# BMS_Schematic.net
KiCad netlist of a schematic drawn in EAGLE
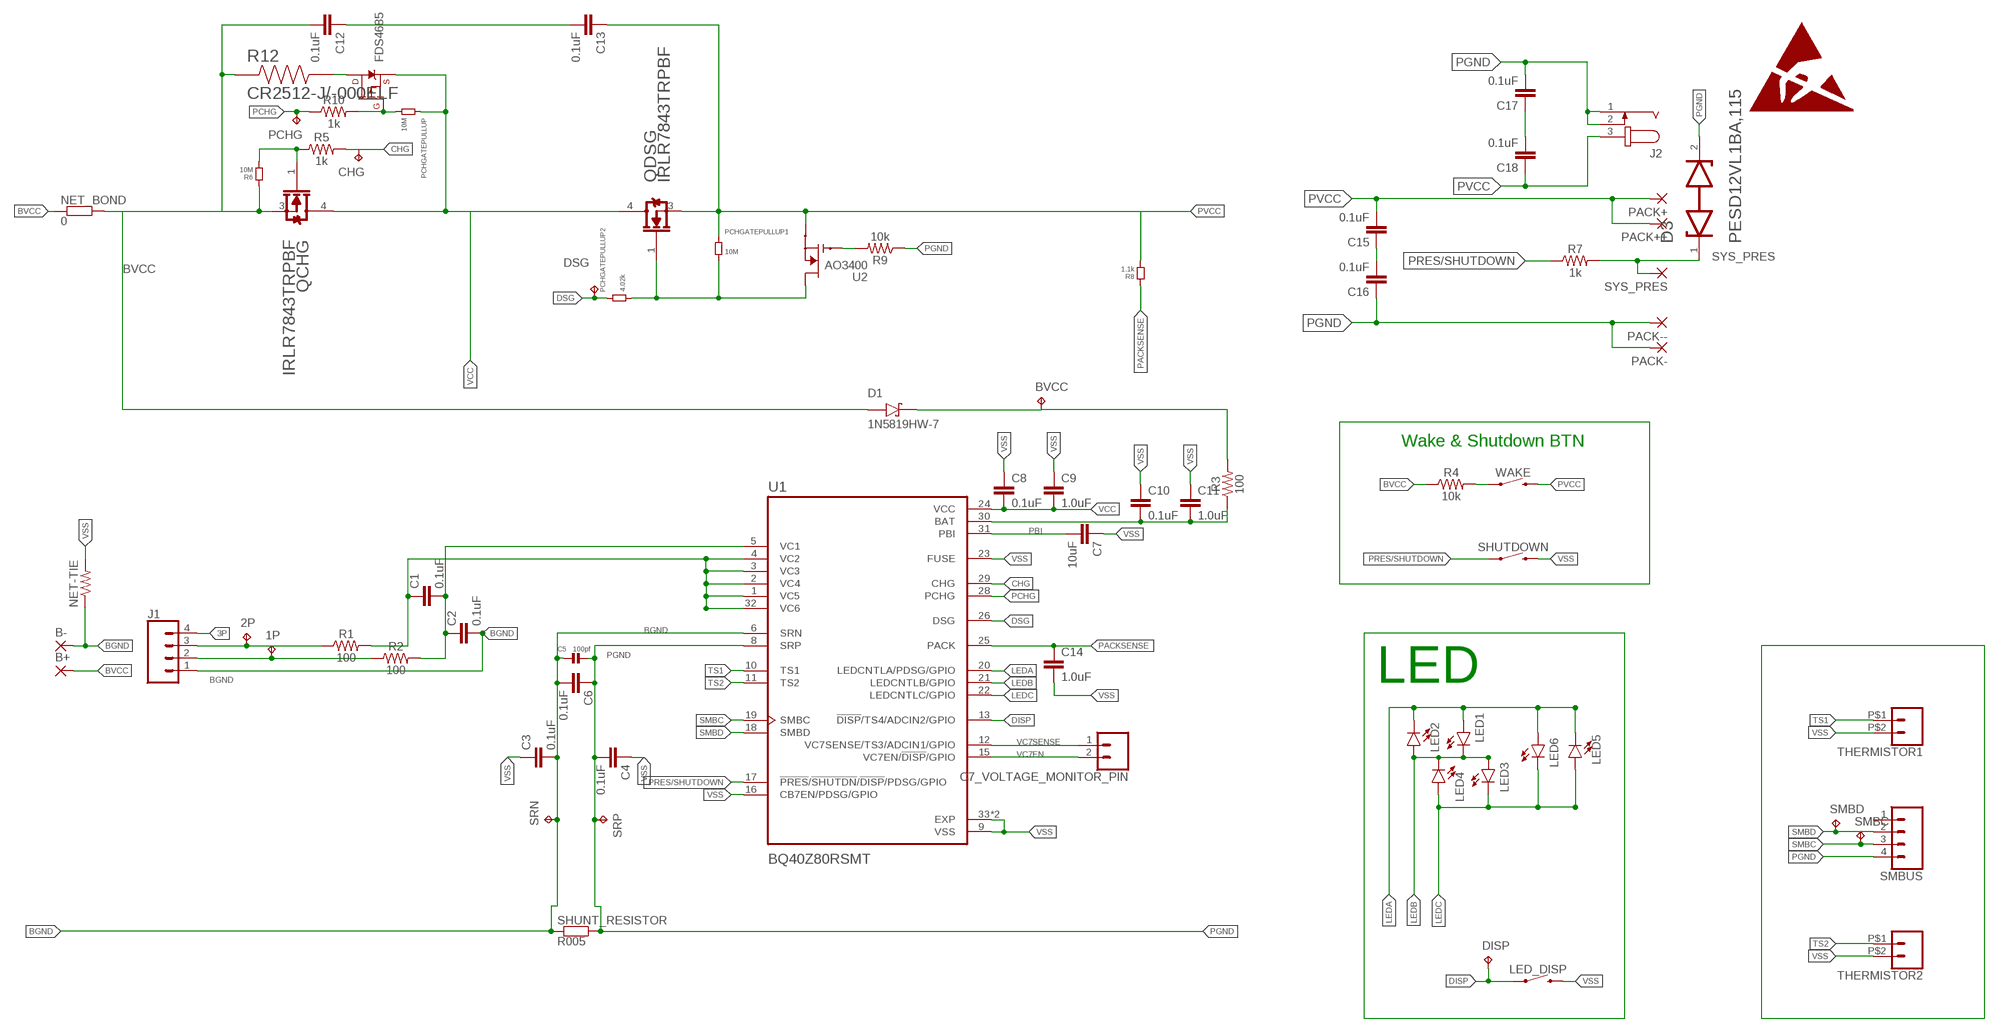
[diagram p0: schematic, sheet 1]

(export (version "E")
  (design (tool "Eeschema 10.0.6"))
  (components
    (comp (ref "1P")
      (value "TPTP10R")
      (footprint "eagle-import:TP10R")
      (libsource (lib "eagle-import") (part "TPTP10R"))
    )
    (comp (ref "2P")
      (value "TPTP10R")
      (footprint "eagle-import:TP10R")
      (libsource (lib "eagle-import") (part "TPTP10R"))
    )
    (comp (ref "B+")
      (value "WIREPADSMD5-2,5")
      (footprint "eagle-import:5-2,5")
      (libsource (lib "eagle-import") (part "WIREPADSMD5-2,5"))
    )
    (comp (ref "B-")
      (value "WIREPADSMD5-2,5")
      (footprint "eagle-import:5-2,5")
      (libsource (lib "eagle-import") (part "WIREPADSMD5-2,5"))
    )
    (comp (ref "BVCC")
      (value "TPTP10R")
      (footprint "eagle-import:TP10R")
      (libsource (lib "eagle-import") (part "TPTP10R"))
    )
    (comp (ref "C1")
      (value "0.1uF")
      (footprint "eagle-import:0603")
      (libsource (lib "eagle-import") (part "0.1UF-0603-25V-5%"))
    )
    (comp (ref "C2")
      (value "0.1uF")
      (footprint "eagle-import:0603")
      (libsource (lib "eagle-import") (part "0.1UF-0603-25V-5%"))
    )
    (comp (ref "C3")
      (value "0.1uF")
      (footprint "eagle-import:0603")
      (libsource (lib "eagle-import") (part "0.1UF-0603-25V-5%"))
    )
    (comp (ref "C4")
      (value "0.1uF")
      (footprint "eagle-import:0603")
      (libsource (lib "eagle-import") (part "0.1UF-0603-25V-5%"))
    )
    (comp (ref "C5")
      (value "100pf")
      (footprint "eagle-import:0805")
      (libsource (lib "eagle-import") (part "CAPACITOR.0805"))
    )
    (comp (ref "C6")
      (value "0.1uF")
      (footprint "eagle-import:0603")
      (libsource (lib "eagle-import") (part "0.1UF-0603-25V-5%"))
    )
    (comp (ref "C7")
      (value "10uF")
      (footprint "eagle-import:0603")
      (libsource (lib "eagle-import") (part "10UF-0603-6.3V-20%"))
    )
    (comp (ref "C7_VOLTAGE_MONITOR_PIN")
      (value "CONN_02")
      (footprint "eagle-import:1X02")
      (libsource (lib "eagle-import") (part "CONN_02"))
    )
    (comp (ref "C8")
      (value "0.1uF")
      (footprint "eagle-import:0603")
      (libsource (lib "eagle-import") (part "0.1UF-0603-25V-(+80/-20%)"))
    )
    (comp (ref "C9")
      (value "1.0uF")
      (footprint "eagle-import:0603")
      (libsource (lib "eagle-import") (part "1.0UF-0603-16V-10%-X7R"))
    )
    (comp (ref "C10")
      (value "0.1uF")
      (footprint "eagle-import:0603")
      (libsource (lib "eagle-import") (part "0.1UF-0603-25V-(+80/-20%)"))
    )
    (comp (ref "C11")
      (value "1.0uF")
      (footprint "eagle-import:0603")
      (libsource (lib "eagle-import") (part "1.0UF-0603-16V-10%-X7R"))
    )
    (comp (ref "C12")
      (value "0.1uF")
      (footprint "eagle-import:0603")
      (libsource (lib "eagle-import") (part "0.1UF-0603-25V-(+80/-20%)"))
    )
    (comp (ref "C13")
      (value "0.1uF")
      (footprint "eagle-import:0603")
      (libsource (lib "eagle-import") (part "0.1UF-0603-25V-(+80/-20%)"))
    )
    (comp (ref "C14")
      (value "1.0uF")
      (footprint "eagle-import:0603")
      (libsource (lib "eagle-import") (part "1.0UF-0603-16V-10%-X7R"))
    )
    (comp (ref "C15")
      (value "0.1uF")
      (footprint "eagle-import:0603")
      (libsource (lib "eagle-import") (part "0.1UF-0603-25V-(+80/-20%)"))
    )
    (comp (ref "C16")
      (value "0.1uF")
      (footprint "eagle-import:0603")
      (libsource (lib "eagle-import") (part "0.1UF-0603-25V-(+80/-20%)"))
    )
    (comp (ref "C17")
      (value "0.1uF")
      (footprint "eagle-import:0603")
      (libsource (lib "eagle-import") (part "0.1UF-0603-25V-(+80/-20%)"))
    )
    (comp (ref "C18")
      (value "0.1uF")
      (footprint "eagle-import:0603")
      (libsource (lib "eagle-import") (part "0.1UF-0603-25V-(+80/-20%)"))
    )
    (comp (ref "CHG")
      (value "TPTP10R")
      (footprint "eagle-import:TP10R")
      (libsource (lib "eagle-import") (part "TPTP10R"))
    )
    (comp (ref "D1")
      (value "1N5819HW-7")
      (footprint "eagle-import:SOD3715X145N")
      (fields (field (name "MF") "Diodes Inc."))
      (libsource (lib "eagle-import") (part "1N5819HW-7"))
    )
    (comp (ref "D3")
      (value "NEXPERIA_PESD12VL1BA,115NEXPERIA_PESD12VL1BA,115_0_0")
      (footprint "eagle-import:NEXPERIA_PESD12VL1BA,115_0")
      (fields
        (field (name "DIGIKEY_PART_NUMBER") "1727-3808-1-ND")
        (field (name "MF") "Nexperia")
        (field (name "MOUSER_PART_NUMBER") "771-PESD12VL1BA-T/R")
      )
      (libsource (lib "eagle-import") (part "NEXPERIA_PESD12VL1BA,115NEXPERIA_PESD12VL1BA,115_0_0"))
    )
    (comp (ref "DISP")
      (value "TPTP10R")
      (footprint "eagle-import:TP10R")
      (libsource (lib "eagle-import") (part "TPTP10R"))
    )
    (comp (ref "DSG")
      (value "TPTP10R")
      (footprint "eagle-import:TP10R")
      (libsource (lib "eagle-import") (part "TPTP10R"))
    )
    (comp (ref "J1")
      (value "CONN_04JST-PTH")
      (footprint "eagle-import:JST-4-PTH")
      (libsource (lib "eagle-import") (part "CONN_04JST-PTH"))
    )
    (comp (ref "J2")
      (value "JACK-PLUG0")
      (footprint "eagle-import:SPC4077")
      (libsource (lib "eagle-import") (part "JACK-PLUG0"))
    )
    (comp (ref "LED1")
      (value "GREEN")
      (footprint "eagle-import:LED-0603")
      (libsource (lib "eagle-import") (part "LED-GREEN0603"))
    )
    (comp (ref "LED2")
      (value "GREEN")
      (footprint "eagle-import:LED-0603")
      (libsource (lib "eagle-import") (part "LED-GREEN0603"))
    )
    (comp (ref "LED3")
      (value "GREEN")
      (footprint "eagle-import:LED-0603")
      (libsource (lib "eagle-import") (part "LED-GREEN0603"))
    )
    (comp (ref "LED4")
      (value "GREEN")
      (footprint "eagle-import:LED-0603")
      (libsource (lib "eagle-import") (part "LED-GREEN0603"))
    )
    (comp (ref "LED5")
      (value "GREEN")
      (footprint "eagle-import:LED-0603")
      (libsource (lib "eagle-import") (part "LED-GREEN0603"))
    )
    (comp (ref "LED6")
      (value "GREEN")
      (footprint "eagle-import:LED-0603")
      (libsource (lib "eagle-import") (part "LED-GREEN0603"))
    )
    (comp (ref "LED_DISP")
      (value "MOMENTARY-SWITCH-SPST-SMD-6.0X3.5MM")
      (footprint "eagle-import:TACTILE_SWITCH_SMD_6.0X3.5MM")
      (libsource (lib "eagle-import") (part "MOMENTARY-SWITCH-SPST-SMD-6.0X3.5MM"))
    )
    (comp (ref "NET-TIE")
      (value "0")
      (footprint "eagle-import:0402-TIGHT")
      (libsource (lib "eagle-import") (part "0OHM-0402T-1/10W"))
    )
    (comp (ref "NET_BOND")
      (value "0")
      (footprint "eagle-import:BVS")
      (libsource (lib "eagle-import") (part "BVS"))
    )
    (comp (ref "PACK+")
      (value "WIREPADSMD5-2,5")
      (footprint "eagle-import:5-2,5")
      (libsource (lib "eagle-import") (part "WIREPADSMD5-2,5"))
    )
    (comp (ref "PACK++")
      (value "WIREPADSMD5-2,5")
      (footprint "eagle-import:5-2,5")
      (libsource (lib "eagle-import") (part "WIREPADSMD5-2,5"))
    )
    (comp (ref "PACK-")
      (value "WIREPADSMD5-2,5")
      (footprint "eagle-import:5-2,5")
      (libsource (lib "eagle-import") (part "WIREPADSMD5-2,5"))
    )
    (comp (ref "PACK--")
      (value "WIREPADSMD5-2,5")
      (footprint "eagle-import:5-2,5")
      (libsource (lib "eagle-import") (part "WIREPADSMD5-2,5"))
    )
    (comp (ref "PCHG")
      (value "TPTP10R")
      (footprint "eagle-import:TP10R")
      (libsource (lib "eagle-import") (part "TPTP10R"))
    )
    (comp (ref "PCHGATEPULLUP")
      (value "10M")
      (footprint "eagle-import:0805")
      (libsource (lib "eagle-import") (part "RESISTOR.0805"))
    )
    (comp (ref "PCHGATEPULLUP1")
      (value "10M")
      (footprint "eagle-import:0805")
      (libsource (lib "eagle-import") (part "RESISTOR.0805"))
    )
    (comp (ref "PCHGATEPULLUP2")
      (value "4.02k")
      (footprint "eagle-import:0805")
      (libsource (lib "eagle-import") (part "RESISTOR.0805"))
    )
    (comp (ref "QCHG")
      (value "INFINEON_IRLR7843TRPBFINFINEON_IRLR7843TRPBF_0_0")
      (footprint "eagle-import:INFINEON_IRLR7843TRPBF_0")
      (fields
        (field (name "DIGIKEY_PART_NUMBER") "IRLR7843PBFCT-ND")
        (field (name "MF") "Infineon")
        (field (name "MOUSER_PART_NUMBER") "942-IRLR7843TRPBF")
      )
      (libsource (lib "eagle-import") (part "INFINEON_IRLR7843TRPBFINFINEON_IRLR7843TRPBF_0_0"))
    )
    (comp (ref "QDSG")
      (value "INFINEON_IRLR7843TRPBFINFINEON_IRLR7843TRPBF_0_0")
      (footprint "eagle-import:INFINEON_IRLR7843TRPBF_0")
      (fields
        (field (name "DIGIKEY_PART_NUMBER") "IRLR7843PBFCT-ND")
        (field (name "MF") "Infineon")
        (field (name "MOUSER_PART_NUMBER") "942-IRLR7843TRPBF")
      )
      (libsource (lib "eagle-import") (part "INFINEON_IRLR7843TRPBFINFINEON_IRLR7843TRPBF_0_0"))
    )
    (comp (ref "R1")
      (value "100")
      (footprint "eagle-import:0603")
      (libsource (lib "eagle-import") (part "100OHM-0603-1/10W-1%"))
    )
    (comp (ref "R2")
      (value "100")
      (footprint "eagle-import:0603")
      (libsource (lib "eagle-import") (part "100OHM-0603-1/10W-1%"))
    )
    (comp (ref "R3")
      (value "100")
      (footprint "eagle-import:0603")
      (libsource (lib "eagle-import") (part "100OHM-0603-1/10W-1%"))
    )
    (comp (ref "R4")
      (value "10k")
      (footprint "eagle-import:0603")
      (libsource (lib "eagle-import") (part "10KOHM-0603-1/10W-1%"))
    )
    (comp (ref "R5")
      (value "1k")
      (footprint "eagle-import:0603")
      (libsource (lib "eagle-import") (part "1KOHM-0603-1/10W-1%"))
    )
    (comp (ref "R6")
      (value "10M")
      (footprint "eagle-import:0805")
      (libsource (lib "eagle-import") (part "RESISTOR.0805"))
    )
    (comp (ref "R7")
      (value "1k")
      (footprint "eagle-import:0603")
      (libsource (lib "eagle-import") (part "1KOHM-0603-1/10W-1%"))
    )
    (comp (ref "R8")
      (value "1.1k")
      (footprint "eagle-import:0805")
      (libsource (lib "eagle-import") (part "RESISTOR.0805"))
    )
    (comp (ref "R9")
      (value "10k")
      (footprint "eagle-import:0603")
      (libsource (lib "eagle-import") (part "10KOHM-0603-1/10W-1%"))
    )
    (comp (ref "R10")
      (value "1k")
      (footprint "eagle-import:0603")
      (libsource (lib "eagle-import") (part "1KOHM-0603-1/10W-1%"))
    )
    (comp (ref "R12")
      (value "CR2512-J/-000ELF")
      (footprint "eagle-import:RESC6331X75N")
      (fields (field (name "MF") "Bourns"))
      (libsource (lib "eagle-import") (part "CR2512-J/-000ELF"))
    )
    (comp (ref "SHUNT_RESISTOR")
      (value "R005")
      (footprint "eagle-import:BVS")
      (libsource (lib "eagle-import") (part "BVS"))
    )
    (comp (ref "SHUTDOWN")
      (value "MOMENTARY-SWITCH-SPST-SMD-6.0X3.5MM")
      (footprint "eagle-import:TACTILE_SWITCH_SMD_6.0X3.5MM")
      (libsource (lib "eagle-import") (part "MOMENTARY-SWITCH-SPST-SMD-6.0X3.5MM"))
    )
    (comp (ref "SMBC")
      (value "TPTP10R")
      (footprint "eagle-import:TP10R")
      (libsource (lib "eagle-import") (part "TPTP10R"))
    )
    (comp (ref "SMBD")
      (value "TPTP10R")
      (footprint "eagle-import:TP10R")
      (libsource (lib "eagle-import") (part "TPTP10R"))
    )
    (comp (ref "SMBUS")
      (value "CONN_04JST-SMD-LOCKING")
      (footprint "eagle-import:JST-4-SMD-1.25MM-LOCKING")
      (libsource (lib "eagle-import") (part "CONN_04JST-SMD-LOCKING"))
    )
    (comp (ref "SRN")
      (value "TPTP10R")
      (footprint "eagle-import:TP10R")
      (libsource (lib "eagle-import") (part "TPTP10R"))
    )
    (comp (ref "SRP")
      (value "TPTP10R")
      (footprint "eagle-import:TP10R")
      (libsource (lib "eagle-import") (part "TPTP10R"))
    )
    (comp (ref "SYS_PRES")
      (value "SMD2")
      (footprint "eagle-import:SMD1,27-2,54")
      (libsource (lib "eagle-import") (part "SMD2"))
    )
    (comp (ref "THERMISTOR1")
      (value "SOLDER_PAD_2")
      (footprint "eagle-import:SOLDER_PAD_2")
      (libsource (lib "eagle-import") (part "SOLDER_PAD_2"))
    )
    (comp (ref "THERMISTOR2")
      (value "SOLDER_PAD_2")
      (footprint "eagle-import:SOLDER_PAD_2")
      (libsource (lib "eagle-import") (part "SOLDER_PAD_2"))
    )
    (comp (ref "U$2")
      (value "FDS4685")
      (footprint "eagle-import:SOIC127P600X150-8N")
      (libsource (lib "eagle-import") (part "FDS4685"))
    )
    (comp (ref "U1")
      (value "BQ40Z80RSMT")
      (footprint "eagle-import:QFN40P400X400X100-33N")
      (fields (field (name "MF") "Texas Instruments"))
      (libsource (lib "eagle-import") (part "BQ40Z80RSMT"))
    )
    (comp (ref "U2")
      (value "AO3400")
      (footprint "eagle-import:SOT23")
      (fields (field (name "MF") "Alpha &"))
      (libsource (lib "eagle-import") (part "AO3400"))
    )
    (comp (ref "WAKE")
      (value "MOMENTARY-SWITCH-SPST-SMD-6.0X3.5MM")
      (footprint "eagle-import:TACTILE_SWITCH_SMD_6.0X3.5MM")
      (libsource (lib "eagle-import") (part "MOMENTARY-SWITCH-SPST-SMD-6.0X3.5MM"))
    )
  )
  (nets
    (net (code "1") (name "/PBI") (class "Default")
      (node (ref "C7") (pin "2") (pinfunction "2_2") (pintype "passive"))
      (node (ref "U1") (pin "31") (pinfunction "PBI_31") (pintype "power_in"))
    )
    (net (code "2") (name "/SYS_PRES") (class "Default")
      (node (ref "D3") (pin "1") (pinfunction "CATHODE_1_1") (pintype "passive"))
      (node (ref "R7") (pin "2") (pinfunction "2_2") (pintype "passive"))
      (node (ref "SYS_PRES") (pin "1") (pinfunction "P_1") (pintype "passive"))
    )
    (net (code "3") (name "/VC7EN") (class "Default")
      (node (ref "C7_VOLTAGE_MONITOR_PIN") (pin "2") (pinfunction "2_2") (pintype "passive"))
      (node (ref "U1") (pin "15") (pinfunction "VC7EN/~{DISP}/GPIO_15") (pintype "bidirectional"))
    )
    (net (code "4") (name "/VC7SENSE") (class "Default")
      (node (ref "C7_VOLTAGE_MONITOR_PIN") (pin "1") (pinfunction "1_1") (pintype "passive"))
      (node (ref "U1") (pin "12") (pinfunction "VC7SENSE/TS3/ADCIN1/GPIO_12") (pintype "bidirectional"))
    )
    (net (code "5") (name "3P") (class "Default")
      (node (ref "J1") (pin "4") (pinfunction "4_4") (pintype "passive"))
    )
    (net (code "6") (name "BGND") (class "Default")
      (node (ref "B-") (pin "1") (pinfunction "P_1") (pintype "passive"))
      (node (ref "C2") (pin "2") (pinfunction "2_2") (pintype "passive"))
      (node (ref "C3") (pin "2") (pinfunction "2_2") (pintype "passive"))
      (node (ref "C5") (pin "1") (pinfunction "1_1") (pintype "bidirectional"))
      (node (ref "C6") (pin "2") (pinfunction "2_2") (pintype "passive"))
      (node (ref "J1") (pin "1") (pinfunction "1_1") (pintype "passive"))
      (node (ref "NET-TIE") (pin "1") (pinfunction "1_1") (pintype "passive"))
      (node (ref "SHUNT_RESISTOR") (pin "2") (pinfunction "2_2") (pintype "passive"))
      (node (ref "SRN") (pin "TP") (pinfunction "TP_TP") (pintype "input"))
      (node (ref "U1") (pin "6") (pinfunction "SRN_6") (pintype "input"))
    )
    (net (code "7") (name "BVCC") (class "Default")
      (node (ref "B+") (pin "1") (pinfunction "P_1") (pintype "passive"))
      (node (ref "C12") (pin "2") (pinfunction "2_2") (pintype "passive"))
      (node (ref "D1") (pin "A") (pinfunction "A_A") (pintype "passive"))
      (node (ref "NET_BOND") (pin "1") (pinfunction "1_1") (pintype "passive"))
      (node (ref "NET_BOND") (pin "2") (pinfunction "2_2") (pintype "passive"))
      (node (ref "QCHG") (pin "3") (pinfunction "SOURCE_3") (pintype "passive"))
      (node (ref "R12") (pin "1") (pinfunction "1_1") (pintype "passive"))
      (node (ref "R4") (pin "1") (pinfunction "1_1") (pintype "passive"))
      (node (ref "R6") (pin "1") (pinfunction "1_1") (pintype "bidirectional"))
    )
    (net (code "8") (name "CHG") (class "Default")
      (node (ref "CHG") (pin "TP") (pinfunction "TP_TP") (pintype "input"))
      (node (ref "R5") (pin "2") (pinfunction "2_2") (pintype "passive"))
      (node (ref "U1") (pin "29") (pinfunction "CHG_29") (pintype "output"))
    )
    (net (code "9") (name "DISP") (class "Default")
      (node (ref "DISP") (pin "TP") (pinfunction "TP_TP") (pintype "input"))
      (node (ref "LED_DISP") (pin "1") (pinfunction "1_1") (pintype "passive"))
      (node (ref "U1") (pin "13") (pinfunction "~{DISP}/TS4/ADCIN2/GPIO_13") (pintype "bidirectional"))
    )
    (net (code "10") (name "DSG") (class "Default")
      (node (ref "DSG") (pin "TP") (pinfunction "TP_TP") (pintype "input"))
      (node (ref "PCHGATEPULLUP2") (pin "1") (pinfunction "1_1") (pintype "bidirectional"))
      (node (ref "U1") (pin "26") (pinfunction "DSG_26") (pintype "output"))
    )
    (net (code "11") (name "LEDA") (class "Default")
      (node (ref "LED1") (pin "A") (pinfunction "A_A") (pintype "passive"))
      (node (ref "LED2") (pin "C") (pinfunction "C_C") (pintype "passive"))
      (node (ref "LED5") (pin "C") (pinfunction "C_C") (pintype "passive"))
      (node (ref "LED6") (pin "A") (pinfunction "A_A") (pintype "passive"))
      (node (ref "U1") (pin "20") (pinfunction "LEDCNTLA/PDSG/GPIO_20") (pintype "output"))
    )
    (net (code "12") (name "LEDB") (class "Default")
      (node (ref "LED1") (pin "C") (pinfunction "C_C") (pintype "passive"))
      (node (ref "LED2") (pin "A") (pinfunction "A_A") (pintype "passive"))
      (node (ref "LED3") (pin "A") (pinfunction "A_A") (pintype "passive"))
      (node (ref "LED4") (pin "C") (pinfunction "C_C") (pintype "passive"))
      (node (ref "U1") (pin "21") (pinfunction "LEDCNTLB/GPIO_21") (pintype "output"))
    )
    (net (code "13") (name "LEDC") (class "Default")
      (node (ref "LED3") (pin "C") (pinfunction "C_C") (pintype "passive"))
      (node (ref "LED4") (pin "A") (pinfunction "A_A") (pintype "passive"))
      (node (ref "LED5") (pin "A") (pinfunction "A_A") (pintype "passive"))
      (node (ref "LED6") (pin "C") (pinfunction "C_C") (pintype "passive"))
      (node (ref "U1") (pin "22") (pinfunction "LEDCNTLC/GPIO_22") (pintype "output"))
    )
    (net (code "14") (name "Net-(1P-PadTP)") (class "Default")
      (node (ref "1P") (pin "TP") (pinfunction "TP_TP") (pintype "input"))
      (node (ref "J1") (pin "2") (pinfunction "2_2") (pintype "passive"))
      (node (ref "R2") (pin "1") (pinfunction "1_1") (pintype "passive"))
    )
    (net (code "15") (name "Net-(2P-PadTP)") (class "Default")
      (node (ref "2P") (pin "TP") (pinfunction "TP_TP") (pintype "input"))
      (node (ref "J1") (pin "3") (pinfunction "3_3") (pintype "passive"))
      (node (ref "R1") (pin "1") (pinfunction "1_1") (pintype "passive"))
    )
    (net (code "16") (name "Net-(C12-Pad1)") (class "Default")
      (node (ref "C12") (pin "1") (pinfunction "1_1") (pintype "passive"))
      (node (ref "C13") (pin "2") (pinfunction "2_2") (pintype "passive"))
    )
    (net (code "17") (name "Net-(C15-Pad1)") (class "Default")
      (node (ref "C15") (pin "1") (pinfunction "1_1") (pintype "passive"))
      (node (ref "C16") (pin "2") (pinfunction "2_2") (pintype "passive"))
    )
    (net (code "18") (name "Net-(C17-Pad1)") (class "Default")
      (node (ref "C17") (pin "1") (pinfunction "1_1") (pintype "passive"))
      (node (ref "C18") (pin "2") (pinfunction "2_2") (pintype "passive"))
    )
    (net (code "19") (name "Net-(D1-K)") (class "Default")
      (node (ref "BVCC") (pin "TP") (pinfunction "TP_TP") (pintype "input"))
      (node (ref "D1") (pin "C") (pinfunction "K_C") (pintype "passive"))
      (node (ref "R3") (pin "2") (pinfunction "2_2") (pintype "passive"))
    )
    (net (code "20") (name "Net-(QCHG-GATE)") (class "Default")
      (node (ref "QCHG") (pin "1") (pinfunction "GATE_1") (pintype "passive"))
      (node (ref "R5") (pin "1") (pinfunction "1_1") (pintype "passive"))
      (node (ref "R6") (pin "2") (pinfunction "2_2") (pintype "bidirectional"))
    )
    (net (code "21") (name "Net-(QDSG-GATE)") (class "Default")
      (node (ref "PCHGATEPULLUP1") (pin "2") (pinfunction "2_2") (pintype "bidirectional"))
      (node (ref "PCHGATEPULLUP2") (pin "2") (pinfunction "2_2") (pintype "bidirectional"))
      (node (ref "QDSG") (pin "1") (pinfunction "GATE_1") (pintype "passive"))
      (node (ref "U2") (pin "3") (pinfunction "D_3") (pintype "passive"))
    )
    (net (code "22") (name "Net-(R4-Pad2)") (class "Default")
      (node (ref "R4") (pin "2") (pinfunction "2_2") (pintype "passive"))
      (node (ref "WAKE") (pin "1") (pinfunction "1_1") (pintype "passive"))
    )
    (net (code "23") (name "Net-(R12-Pad2)") (class "Default")
      (node (ref "R12") (pin "2") (pinfunction "2_2") (pintype "passive"))
      (node (ref "U$2") (pin "5") (pinfunction "D_5") (pintype "bidirectional"))
      (node (ref "U$2") (pin "6") (pinfunction "D_6") (pintype "bidirectional"))
      (node (ref "U$2") (pin "7") (pinfunction "D_7") (pintype "bidirectional"))
      (node (ref "U$2") (pin "8") (pinfunction "D_8") (pintype "bidirectional"))
    )
    (net (code "24") (name "Net-(U$2-G)") (class "Default")
      (node (ref "PCHGATEPULLUP") (pin "2") (pinfunction "2_2") (pintype "bidirectional"))
      (node (ref "R10") (pin "2") (pinfunction "2_2") (pintype "passive"))
      (node (ref "U$2") (pin "4") (pinfunction "G_4") (pintype "bidirectional"))
    )
    (net (code "25") (name "Net-(U1-BAT)") (class "Default")
      (node (ref "C10") (pin "2") (pinfunction "2_2") (pintype "passive"))
      (node (ref "C11") (pin "2") (pinfunction "2_2") (pintype "passive"))
      (node (ref "R3") (pin "1") (pinfunction "1_1") (pintype "passive"))
      (node (ref "U1") (pin "30") (pinfunction "BAT_30") (pintype "power_in"))
    )
    (net (code "26") (name "Net-(U1-VC1)") (class "Default")
      (node (ref "C1") (pin "2") (pinfunction "2_2") (pintype "passive"))
      (node (ref "C2") (pin "1") (pinfunction "1_1") (pintype "passive"))
      (node (ref "R2") (pin "2") (pinfunction "2_2") (pintype "passive"))
      (node (ref "U1") (pin "5") (pinfunction "VC1_5") (pintype "input"))
    )
    (net (code "27") (name "Net-(U1-VC2)") (class "Default")
      (node (ref "C1") (pin "1") (pinfunction "1_1") (pintype "passive"))
      (node (ref "R1") (pin "2") (pinfunction "2_2") (pintype "passive"))
      (node (ref "U1") (pin "1") (pinfunction "VC5_1") (pintype "input"))
      (node (ref "U1") (pin "2") (pinfunction "VC4_2") (pintype "input"))
      (node (ref "U1") (pin "3") (pinfunction "VC3_3") (pintype "input"))
      (node (ref "U1") (pin "32") (pinfunction "VC6_32") (pintype "input"))
      (node (ref "U1") (pin "4") (pinfunction "VC2_4") (pintype "input"))
    )
    (net (code "28") (name "Net-(U2-G)") (class "Default")
      (node (ref "R9") (pin "2") (pinfunction "2_2") (pintype "passive"))
      (node (ref "U2") (pin "1") (pinfunction "G_1") (pintype "passive"))
    )
    (net (code "29") (name "PACKSENSE") (class "Default")
      (node (ref "C14") (pin "1") (pinfunction "1_1") (pintype "passive"))
      (node (ref "R8") (pin "1") (pinfunction "1_1") (pintype "bidirectional"))
      (node (ref "U1") (pin "25") (pinfunction "PACK_25") (pintype "input"))
    )
    (net (code "30") (name "PCHG") (class "Default")
      (node (ref "PCHG") (pin "TP") (pinfunction "TP_TP") (pintype "input"))
      (node (ref "R10") (pin "1") (pinfunction "1_1") (pintype "passive"))
      (node (ref "U1") (pin "28") (pinfunction "PCHG_28") (pintype "output"))
    )
    (net (code "31") (name "PGND") (class "Default")
      (node (ref "C16") (pin "1") (pinfunction "1_1") (pintype "passive"))
      (node (ref "C17") (pin "2") (pinfunction "2_2") (pintype "passive"))
      (node (ref "C4") (pin "2") (pinfunction "2_2") (pintype "passive"))
      (node (ref "C5") (pin "2") (pinfunction "2_2") (pintype "bidirectional"))
      (node (ref "C6") (pin "1") (pinfunction "1_1") (pintype "passive"))
      (node (ref "D3") (pin "2") (pinfunction "CATHODE_2_2") (pintype "passive"))
      (node (ref "J2") (pin "1") (pinfunction "1_1") (pintype "passive"))
      (node (ref "J2") (pin "2") (pinfunction "2_2") (pintype "passive"))
      (node (ref "PACK-") (pin "1") (pinfunction "P_1") (pintype "passive"))
      (node (ref "PACK--") (pin "1") (pinfunction "P_1") (pintype "passive"))
      (node (ref "R9") (pin "1") (pinfunction "1_1") (pintype "passive"))
      (node (ref "SHUNT_RESISTOR") (pin "1") (pinfunction "1_1") (pintype "passive"))
      (node (ref "SMBUS") (pin "4") (pinfunction "4_4") (pintype "passive"))
      (node (ref "SRP") (pin "TP") (pinfunction "TP_TP") (pintype "input"))
      (node (ref "U1") (pin "8") (pinfunction "SRP_8") (pintype "input"))
    )
    (net (code "32") (name "PRES{slash}SHUTDOWN") (class "Default")
      (node (ref "R7") (pin "1") (pinfunction "1_1") (pintype "passive"))
      (node (ref "SHUTDOWN") (pin "1") (pinfunction "1_1") (pintype "passive"))
      (node (ref "U1") (pin "17") (pinfunction "~{PRES}/~{SHUTDN}/~{DISP}/PDSG/GPIO_17") (pintype "bidirectional"))
    )
    (net (code "33") (name "PVCC") (class "Default")
      (node (ref "C13") (pin "1") (pinfunction "1_1") (pintype "passive"))
      (node (ref "C15") (pin "2") (pinfunction "2_2") (pintype "passive"))
      (node (ref "C18") (pin "1") (pinfunction "1_1") (pintype "passive"))
      (node (ref "J2") (pin "3") (pinfunction "3_3") (pintype "passive"))
      (node (ref "PACK+") (pin "1") (pinfunction "P_1") (pintype "passive"))
      (node (ref "PACK++") (pin "1") (pinfunction "P_1") (pintype "passive"))
      (node (ref "PCHGATEPULLUP1") (pin "1") (pinfunction "1_1") (pintype "bidirectional"))
      (node (ref "QDSG") (pin "3") (pinfunction "SOURCE_3") (pintype "passive"))
      (node (ref "R8") (pin "2") (pinfunction "2_2") (pintype "bidirectional"))
      (node (ref "U2") (pin "2") (pinfunction "S_2") (pintype "passive"))
      (node (ref "WAKE") (pin "2") (pinfunction "2_2") (pintype "passive"))
    )
    (net (code "34") (name "SMBC") (class "Default")
      (node (ref "SMBC") (pin "TP") (pinfunction "TP_TP") (pintype "input"))
      (node (ref "SMBUS") (pin "3") (pinfunction "3_3") (pintype "passive"))
      (node (ref "U1") (pin "19") (pinfunction "SMBC_19") (pintype "bidirectional"))
    )
    (net (code "35") (name "SMBD") (class "Default")
      (node (ref "SMBD") (pin "TP") (pinfunction "TP_TP") (pintype "input"))
      (node (ref "SMBUS") (pin "2") (pinfunction "2_2") (pintype "passive"))
      (node (ref "U1") (pin "18") (pinfunction "SMBD_18") (pintype "bidirectional"))
    )
    (net (code "36") (name "TS1") (class "Default")
      (node (ref "THERMISTOR1") (pin "P$1") (pinfunction "1_P$1") (pintype "passive"))
      (node (ref "U1") (pin "10") (pinfunction "TS1_10") (pintype "input"))
    )
    (net (code "37") (name "TS2") (class "Default")
      (node (ref "THERMISTOR2") (pin "P$1") (pinfunction "1_P$1") (pintype "passive"))
      (node (ref "U1") (pin "11") (pinfunction "TS2_11") (pintype "input"))
    )
    (net (code "38") (name "VCC") (class "Default")
      (node (ref "C8") (pin "2") (pinfunction "2_2") (pintype "passive"))
      (node (ref "C9") (pin "2") (pinfunction "2_2") (pintype "passive"))
      (node (ref "PCHGATEPULLUP") (pin "1") (pinfunction "1_1") (pintype "bidirectional"))
      (node (ref "QCHG") (pin "4") (pinfunction "DRAIN_4") (pintype "passive"))
      (node (ref "QDSG") (pin "4") (pinfunction "DRAIN_4") (pintype "passive"))
      (node (ref "U$2") (pin "1") (pinfunction "S_1") (pintype "bidirectional"))
      (node (ref "U$2") (pin "2") (pinfunction "S_2") (pintype "bidirectional"))
      (node (ref "U$2") (pin "3") (pinfunction "S_3") (pintype "bidirectional"))
      (node (ref "U1") (pin "24") (pinfunction "VCC_24") (pintype "power_in"))
    )
    (net (code "39") (name "VSS") (class "Default")
      (node (ref "C10") (pin "1") (pinfunction "1_1") (pintype "passive"))
      (node (ref "C11") (pin "1") (pinfunction "1_1") (pintype "passive"))
      (node (ref "C14") (pin "2") (pinfunction "2_2") (pintype "passive"))
      (node (ref "C3") (pin "1") (pinfunction "1_1") (pintype "passive"))
      (node (ref "C4") (pin "1") (pinfunction "1_1") (pintype "passive"))
      (node (ref "C7") (pin "1") (pinfunction "1_1") (pintype "passive"))
      (node (ref "C8") (pin "1") (pinfunction "1_1") (pintype "passive"))
      (node (ref "C9") (pin "1") (pinfunction "1_1") (pintype "passive"))
      (node (ref "LED_DISP") (pin "2") (pinfunction "2_2") (pintype "passive"))
      (node (ref "NET-TIE") (pin "2") (pinfunction "2_2") (pintype "passive"))
      (node (ref "SHUTDOWN") (pin "2") (pinfunction "2_2") (pintype "passive"))
      (node (ref "THERMISTOR1") (pin "P$2") (pinfunction "2_P$2") (pintype "passive"))
      (node (ref "THERMISTOR2") (pin "P$2") (pinfunction "2_P$2") (pintype "passive"))
      (node (ref "U1") (pin "16") (pinfunction "CB7EN/PDSG/GPIO_16") (pintype "bidirectional"))
      (node (ref "U1") (pin "23") (pinfunction "FUSE_23") (pintype "output"))
      (node (ref "U1") (pin "33") (pinfunction "EXP_33") (pintype "power_in"))
      (node (ref "U1") (pin "33_1") (pinfunction "EXP_33_1") (pintype "power_in"))
      (node (ref "U1") (pin "9") (pinfunction "VSS_9") (pintype "power_in"))
    )
    (net (code "40") (name "unconnected-(SMBUS-Pad1)") (class "Default")
      (node (ref "SMBUS") (pin "1") (pinfunction "1_1") (pintype "passive"))
    )
  )
)
